# chicker.net
KiCad netlist of a schematic drawn in Altium Designer
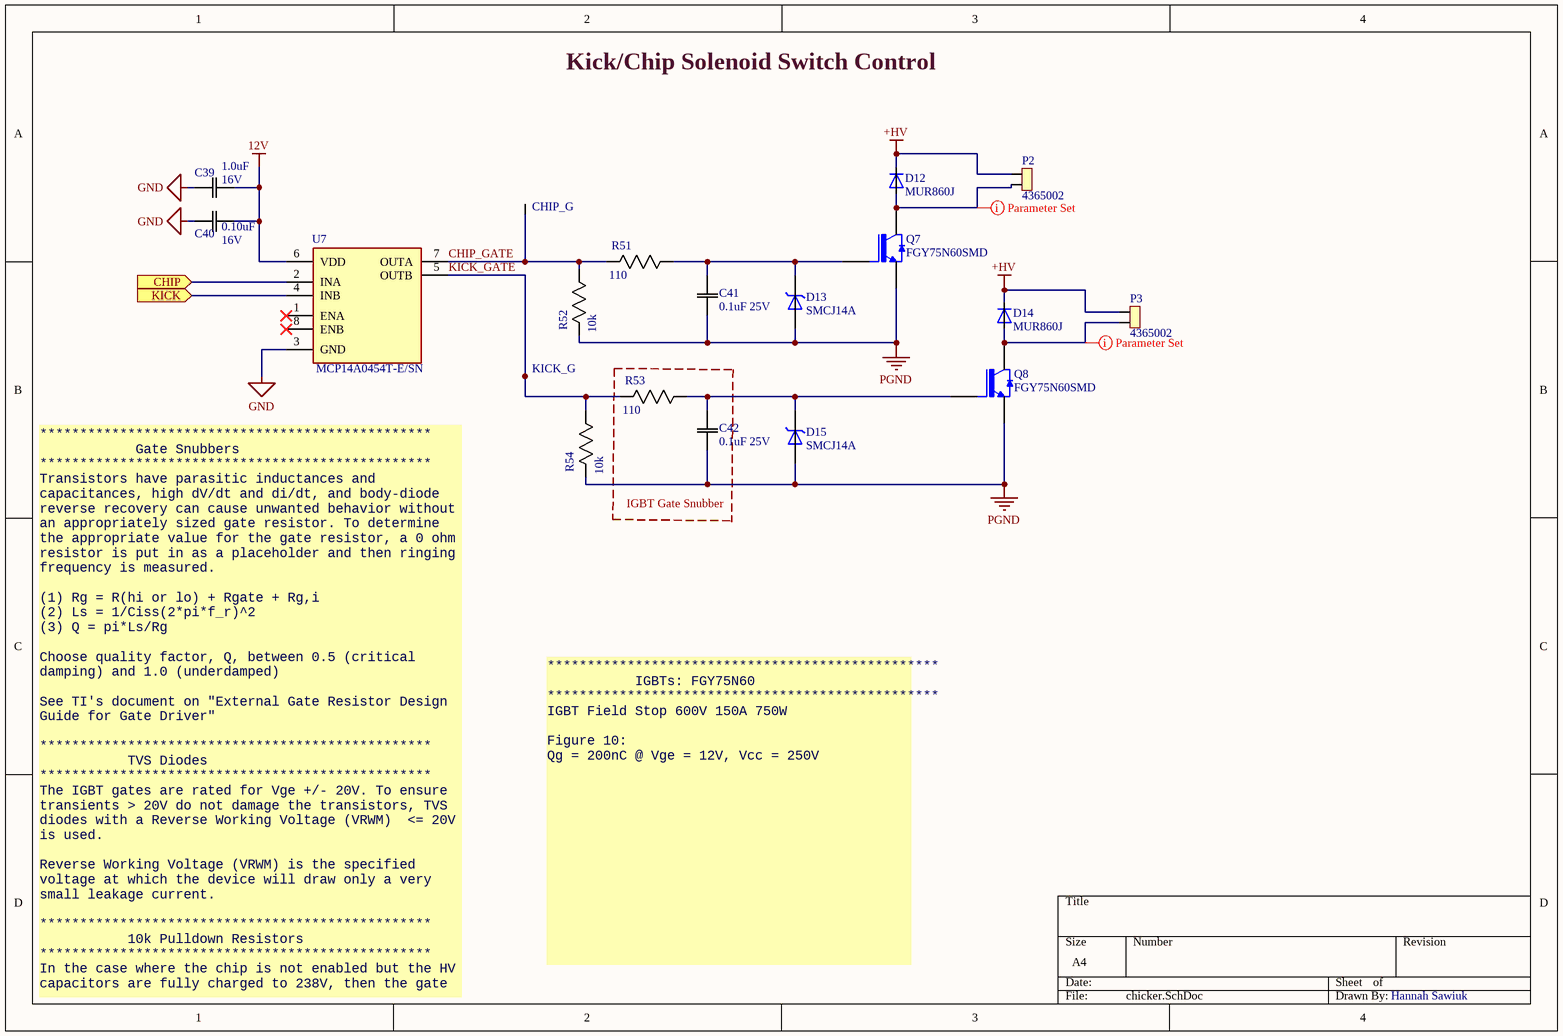
[diagram p0: chicker.SchDoc]

(export (version "E")
  (design (tool "Eeschema 10.0.6"))
  (components
    (comp (ref "C39")
      (value "1.0uF")
      (footprint "0603")
      (description "CAP CER 1.0UF 16V X5R 0603/0805")
      (fields (field (name "TOLERANCE") "10%") (field (name "RATING") "16V"))
      (libsource (lib "AltiumLibraries") (part "CAP 1.0uF 16V"))
    )
    (comp (ref "C40")
      (value "0.10uF")
      (footprint "0603")
      (description "CAP CER 0.10UF 16V X5R 0603/0805")
      (fields (field (name "TOLERANCE") "10%") (field (name "RATING") "16V"))
      (libsource (lib "AltiumLibraries") (part "CAP 0.10uF 16V"))
    )
    (comp (ref "C41")
      (value "0.1uF 25V")
      (footprint "0603")
      (description "CAP CER 0.1UF 25V X7R 0805/0603")
      (fields (field (name "TOLERANCE") "10%"))
      (libsource (lib "AltiumLibraries") (part "CAP 0.1uF 25V"))
    )
    (comp (ref "C42")
      (value "0.1uF 25V")
      (footprint "0603")
      (description "CAP CER 0.1UF 25V X7R 0805/0603")
      (fields (field (name "TOLERANCE") "10%"))
      (libsource (lib "AltiumLibraries") (part "CAP 0.1uF 25V"))
    )
    (comp (ref "CHIP_G")
      (value "Test Point (Via)")
      (footprint "TP")
      (libsource (lib "AltiumLibraries") (part "Test Point (Via)"))
    )
    (comp (ref "D12")
      (value "MUR860J")
      (footprint "DO-214AB-DIODES")
      (description "Diode Standard 600 V 8A Surface Mount SMC")
      (libsource (lib "AltiumLibraries") (part "DIODE FAST 600V 8A"))
    )
    (comp (ref "D13")
      (value "SMCJ14A")
      (footprint "DIOM7959X262N")
      (description "23.2V Clamp 64.7A Ipp Tvs Diode Surface Mount DO-214AB (SMC), VR = 14V, VBR = 15.6V")
      (libsource (lib "AltiumLibraries") (part "DIODE TVS 14VR 15.6VBR"))
    )
    (comp (ref "D14")
      (value "MUR860J")
      (footprint "DO-214AB-DIODES")
      (description "Diode Standard 600 V 8A Surface Mount SMC")
      (libsource (lib "AltiumLibraries") (part "DIODE FAST 600V 8A"))
    )
    (comp (ref "D15")
      (value "SMCJ14A")
      (footprint "DIOM7959X262N")
      (description "23.2V Clamp 64.7A Ipp Tvs Diode Surface Mount DO-214AB (SMC), VR = 14V, VBR = 15.6V")
      (libsource (lib "AltiumLibraries") (part "DIODE TVS 14VR 15.6VBR"))
    )
    (comp (ref "KICK_G")
      (value "Test Point (Via)")
      (footprint "TP")
      (libsource (lib "AltiumLibraries") (part "Test Point (Via)"))
    )
    (comp (ref "P2")
      (value "4365002")
      (footprint "43650-02")
      (description "MOLEX MICROFIT 2CKT RIGHT THRU")
      (fields (field (name "MF") "MOLEX") (field (name "MP") "4365002XX"))
      (libsource (lib "AltiumLibraries") (part "CN MOLEX 4365002XX"))
    )
    (comp (ref "P3")
      (value "4365002")
      (footprint "43650-02")
      (description "MOLEX MICROFIT 2CKT RIGHT THRU")
      (fields (field (name "MF") "MOLEX") (field (name "MP") "4365002XX"))
      (libsource (lib "AltiumLibraries") (part "CN MOLEX 4365002XX"))
    )
    (comp (ref "Q7")
      (value "FGY75N60SMD")
      (footprint "TO-247-3 - FaceDown")
      (description "IGBT Field Stop 600V 150A 750W Through Hole PowerTO-247-3")
      (fields (field (name "MF") "ON Semiconductor") (field (name "POWER") "750W"))
      (libsource (lib "AltiumLibraries") (part "FGY75N60SMD"))
    )
    (comp (ref "Q8")
      (value "FGY75N60SMD")
      (footprint "TO-247-3 - FaceDown")
      (description "IGBT Field Stop 600V 150A 750W Through Hole PowerTO-247-3")
      (fields (field (name "MF") "ON Semiconductor") (field (name "POWER") "750W"))
      (libsource (lib "AltiumLibraries") (part "FGY75N60SMD"))
    )
    (comp (ref "R51")
      (value "110")
      (footprint "0603")
      (description "RES SMD 110 OHM 1% 1/8W 0805/0603")
      (fields (field (name "TOLERANCE") "1%"))
      (libsource (lib "AltiumLibraries") (part "RES 110.0 1/8W - 1%"))
    )
    (comp (ref "R52")
      (value "10k")
      (footprint "0603")
      (description "RES SMD 10K OHM 1% 1/8W 0805/0603")
      (fields (field (name "TOLERANCE") "1%"))
      (libsource (lib "AltiumLibraries") (part "RES 10k 1/8W - 1%"))
    )
    (comp (ref "R53")
      (value "110")
      (footprint "0603")
      (description "RES SMD 110 OHM 1% 1/8W 0805/0603")
      (fields (field (name "TOLERANCE") "1%"))
      (libsource (lib "AltiumLibraries") (part "RES 110.0 1/8W - 1%"))
    )
    (comp (ref "R54")
      (value "10k")
      (footprint "0603")
      (description "RES SMD 10K OHM 1% 1/8W 0805/0603")
      (fields (field (name "TOLERANCE") "1%"))
      (libsource (lib "AltiumLibraries") (part "RES 10k 1/8W - 1%"))
    )
    (comp (ref "U7")
      (value "MCP14A0454T-E/SN")
      (footprint "8-SOIC")
      (description "Low-Side Gate Driver IC Non-Inverting 8-SOIC")
      (libsource (lib "AltiumLibraries") (part "MCP14A0454T-E/SN"))
    )
  )
  (nets
    (net (code "1") (name "+HV") (class "Default")
      (node (ref "D12") (pin "1") (pinfunction "C_1") (pintype "passive"))
      (node (ref "D14") (pin "1") (pinfunction "C_1") (pintype "passive"))
      (node (ref "P2") (pin "1") (pinfunction "1_1") (pintype "passive"))
      (node (ref "P3") (pin "1") (pinfunction "1_1") (pintype "passive"))
    )
    (net (code "2") (name "/CHIP") (class "Default")
      (node (ref "U7") (pin "2") (pinfunction "INA_2") (pintype "passive"))
    )
    (net (code "3") (name "/CHIP_GATE") (class "Default")
      (node (ref "CHIP_G") (pin "1") (pinfunction "1_1") (pintype "passive"))
      (node (ref "R51") (pin "2") (pinfunction "R2_2") (pintype "passive"))
      (node (ref "R52") (pin "1") (pinfunction "R1_1") (pintype "passive"))
      (node (ref "U7") (pin "7") (pinfunction "OUTA_7") (pintype "passive"))
    )
    (net (code "4") (name "/KICK") (class "Default")
      (node (ref "U7") (pin "4") (pinfunction "INB_4") (pintype "passive"))
    )
    (net (code "5") (name "/KICK_GATE") (class "Default")
      (node (ref "KICK_G") (pin "1") (pinfunction "1_1") (pintype "passive"))
      (node (ref "R53") (pin "2") (pinfunction "R2_2") (pintype "passive"))
      (node (ref "R54") (pin "1") (pinfunction "R1_1") (pintype "passive"))
      (node (ref "U7") (pin "5") (pinfunction "OUTB_5") (pintype "passive"))
    )
    (net (code "6") (name "12V") (class "Default")
      (node (ref "C39") (pin "2") (pinfunction "C2_2") (pintype "passive"))
      (node (ref "C40") (pin "2") (pinfunction "C2_2") (pintype "passive"))
      (node (ref "U7") (pin "6") (pinfunction "VDD_6") (pintype "passive"))
    )
    (net (code "7") (name "GND") (class "Default")
      (node (ref "C39") (pin "1") (pinfunction "C1_1") (pintype "passive"))
      (node (ref "C40") (pin "1") (pinfunction "C1_1") (pintype "passive"))
      (node (ref "U7") (pin "3") (pinfunction "GND_3") (pintype "passive"))
    )
    (net (code "8") (name "Net-(C41-C2)") (class "Default")
      (node (ref "C41") (pin "2") (pinfunction "C2_2") (pintype "passive"))
      (node (ref "D13") (pin "C") (pinfunction "C_C") (pintype "passive"))
      (node (ref "Q7") (pin "1") (pinfunction "G_1") (pintype "passive"))
      (node (ref "R51") (pin "1") (pinfunction "R1_1") (pintype "passive"))
    )
    (net (code "9") (name "Net-(C42-C2)") (class "Default")
      (node (ref "C42") (pin "2") (pinfunction "C2_2") (pintype "passive"))
      (node (ref "D15") (pin "C") (pinfunction "C_C") (pintype "passive"))
      (node (ref "Q8") (pin "1") (pinfunction "G_1") (pintype "passive"))
      (node (ref "R53") (pin "1") (pinfunction "R1_1") (pintype "passive"))
    )
    (net (code "10") (name "Net-(D12-A)") (class "Default")
      (node (ref "D12") (pin "2") (pinfunction "A_2") (pintype "passive"))
      (node (ref "P2") (pin "2") (pinfunction "2_2") (pintype "passive"))
      (node (ref "Q7") (pin "2") (pinfunction "C_2") (pintype "passive"))
    )
    (net (code "11") (name "Net-(D14-A)") (class "Default")
      (node (ref "D14") (pin "2") (pinfunction "A_2") (pintype "passive"))
      (node (ref "P3") (pin "2") (pinfunction "2_2") (pintype "passive"))
      (node (ref "Q8") (pin "2") (pinfunction "C_2") (pintype "passive"))
    )
    (net (code "12") (name "PGND") (class "Default")
      (node (ref "C41") (pin "1") (pinfunction "C1_1") (pintype "passive"))
      (node (ref "C42") (pin "1") (pinfunction "C1_1") (pintype "passive"))
      (node (ref "D13") (pin "A") (pinfunction "A_A") (pintype "passive"))
      (node (ref "D15") (pin "A") (pinfunction "A_A") (pintype "passive"))
      (node (ref "Q7") (pin "3") (pinfunction "E_3") (pintype "passive"))
      (node (ref "Q8") (pin "3") (pinfunction "E_3") (pintype "passive"))
      (node (ref "R52") (pin "2") (pinfunction "R2_2") (pintype "passive"))
      (node (ref "R54") (pin "2") (pinfunction "R2_2") (pintype "passive"))
    )
    (net (code "13") (name "unconnected-(U7-ENA-Pad1)") (class "Default")
      (node (ref "U7") (pin "1") (pinfunction "ENA_1") (pintype "passive+no_connect"))
    )
    (net (code "14") (name "unconnected-(U7-ENB-Pad8)") (class "Default")
      (node (ref "U7") (pin "8") (pinfunction "ENB_8") (pintype "passive+no_connect"))
    )
  )
)
